# EvvGC_v1_1.net
KiCad netlist of a schematic drawn in Altium Designer
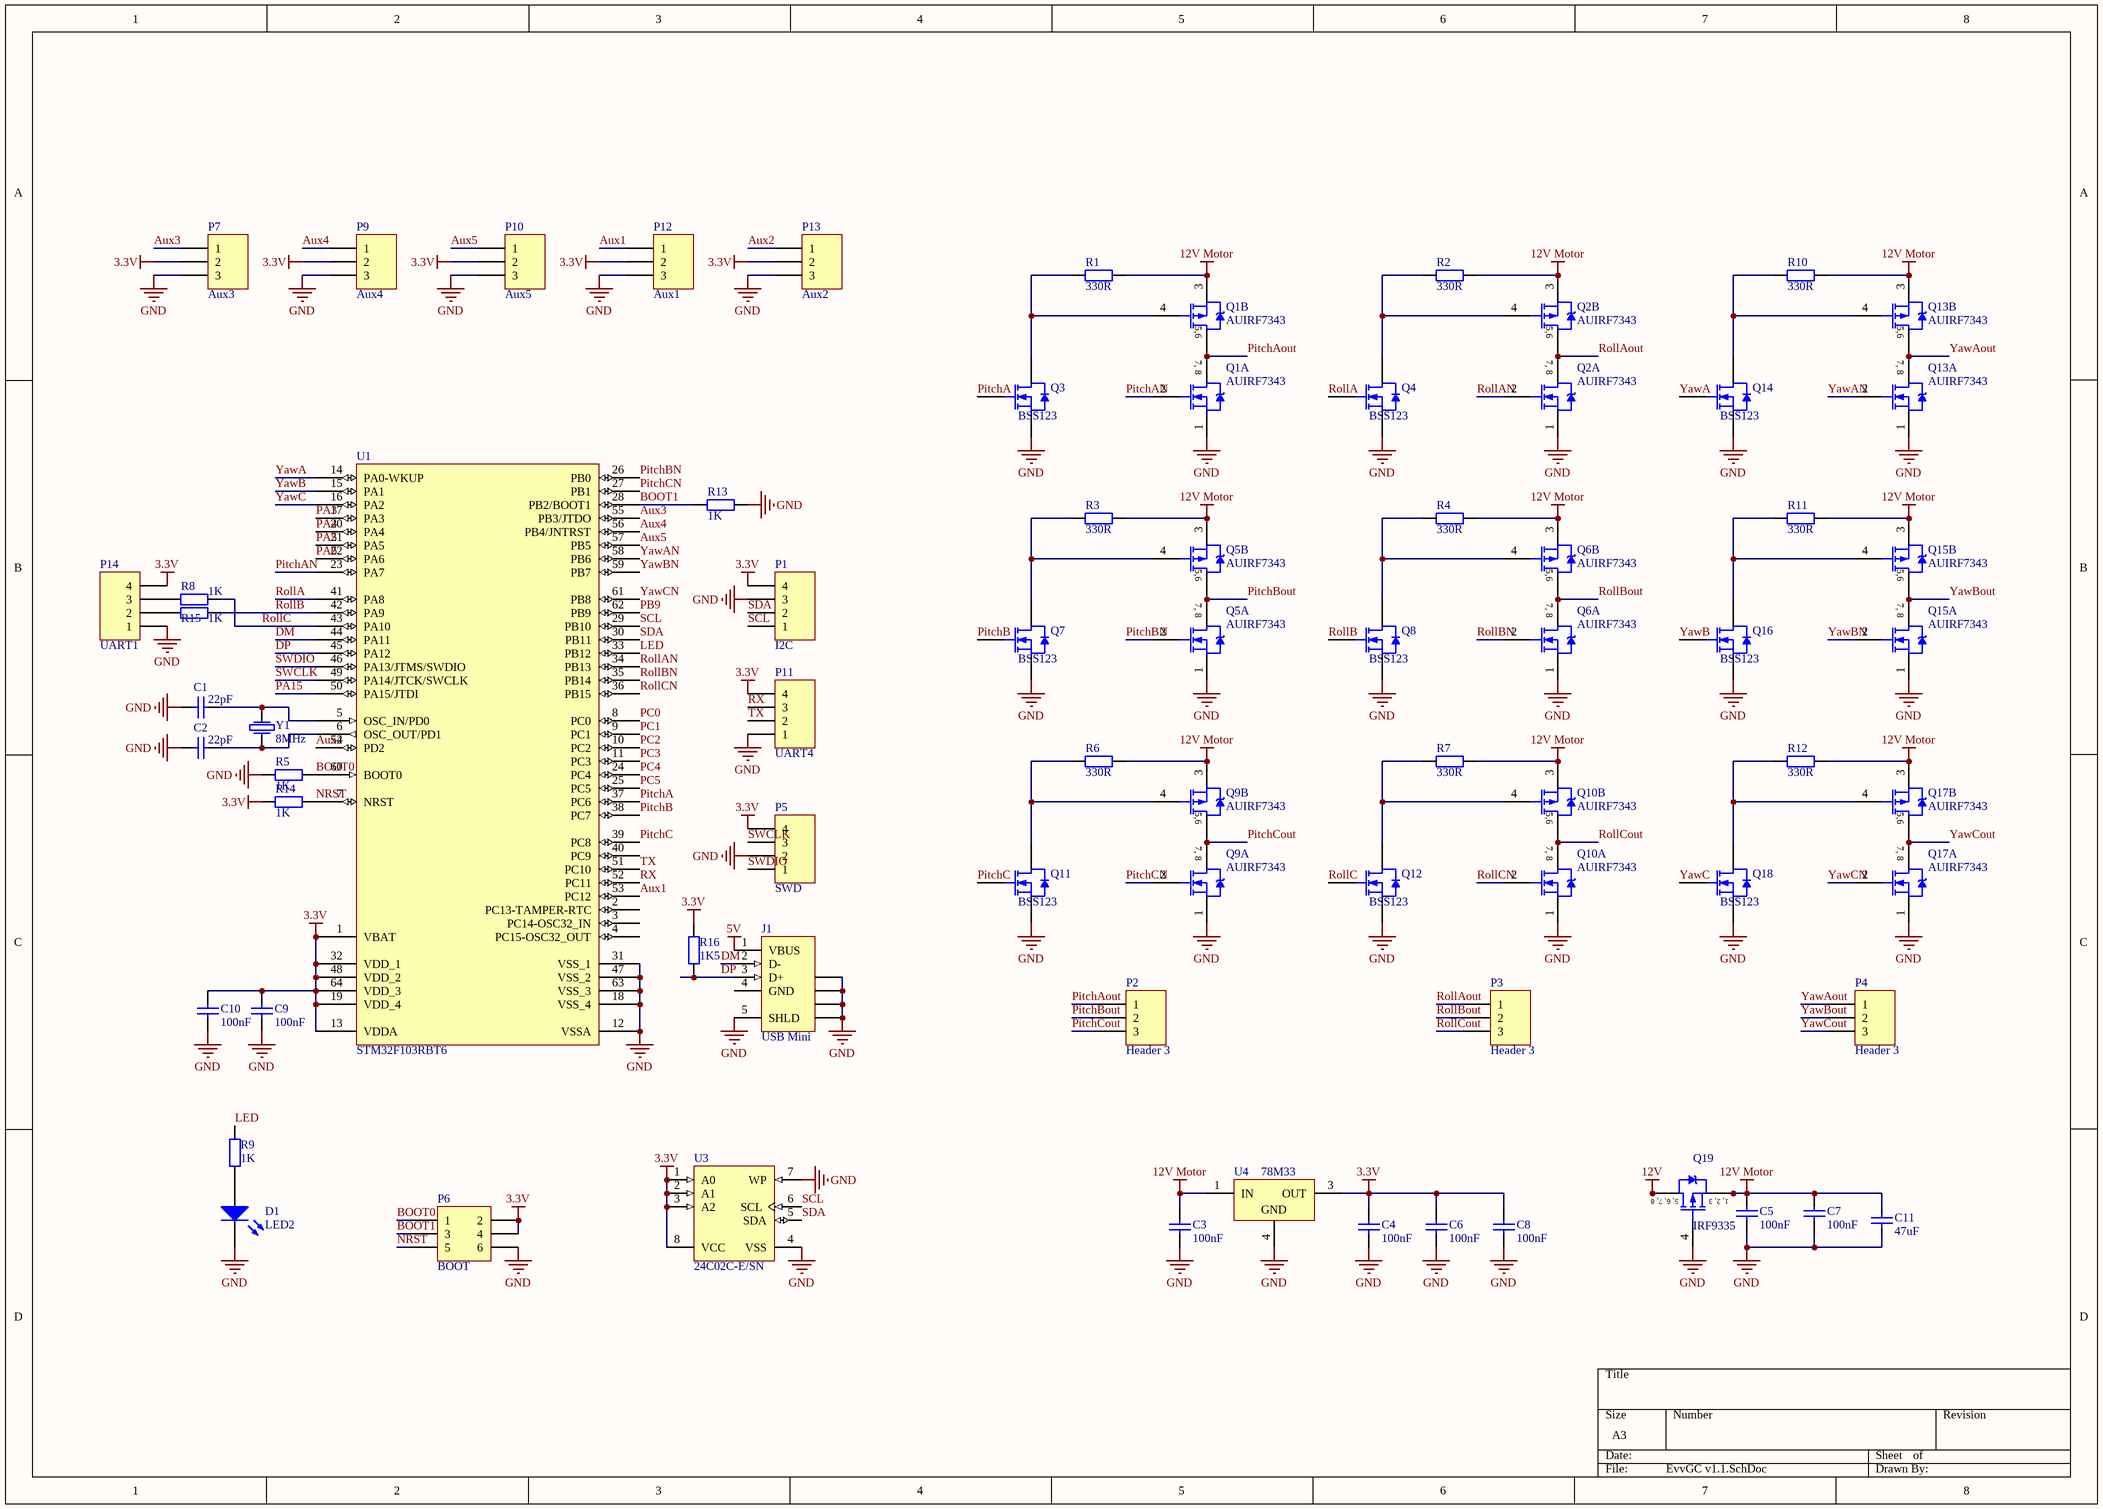
[diagram p0: EvvGC v1.1.SchDoc]

(export (version "E")
  (design (tool "Eeschema 10.0.6"))
  (components
    (comp (ref "C1")
      (value "22pF")
      (footprint "CAPC2012L")
      (description "Capacitor")
      (fields (field (name "Comment") "CAP0805") (field (name "PUBLISHER") "Altium Limited"))
      (libsource (lib "EMotus Components") (part "CAP0805"))
    )
    (comp (ref "C2")
      (value "22pF")
      (footprint "CAPC2012L")
      (description "Capacitor")
      (fields (field (name "Comment") "CAP0805") (field (name "PUBLISHER") "Altium Limited"))
      (libsource (lib "EMotus Components") (part "CAP0805"))
    )
    (comp (ref "C3")
      (value "100nF")
      (footprint "CAPC2012L")
      (description "Capacitor")
      (fields (field (name "Comment") "CAP0805") (field (name "PUBLISHER") "Altium Limited"))
      (libsource (lib "EMotus Components") (part "CAP0805"))
    )
    (comp (ref "C4")
      (value "100nF")
      (footprint "CAPC2012L")
      (description "Capacitor")
      (fields (field (name "Comment") "CAP0805") (field (name "PUBLISHER") "Altium Limited"))
      (libsource (lib "EMotus Components") (part "CAP0805"))
    )
    (comp (ref "C5")
      (value "100nF")
      (footprint "CAPC2012L")
      (description "Capacitor")
      (fields (field (name "Comment") "CAP0805") (field (name "PUBLISHER") "Altium Limited"))
      (libsource (lib "EMotus Components") (part "CAP0805"))
    )
    (comp (ref "C6")
      (value "100nF")
      (footprint "CAPC2012L")
      (description "Capacitor")
      (fields (field (name "Comment") "CAP0805") (field (name "PUBLISHER") "Altium Limited"))
      (libsource (lib "EMotus Components") (part "CAP0805"))
    )
    (comp (ref "C7")
      (value "100nF")
      (footprint "CAPC2012L")
      (description "Capacitor")
      (fields (field (name "Comment") "CAP0805") (field (name "PUBLISHER") "Altium Limited"))
      (libsource (lib "EMotus Components") (part "CAP0805"))
    )
    (comp (ref "C8")
      (value "100nF")
      (footprint "CAPC2012L")
      (description "Capacitor")
      (fields (field (name "Comment") "CAP0805") (field (name "PUBLISHER") "Altium Limited"))
      (libsource (lib "EMotus Components") (part "CAP0805"))
    )
    (comp (ref "C9")
      (value "100nF")
      (footprint "CAPC2012L")
      (description "Capacitor")
      (fields (field (name "Comment") "CAP0805") (field (name "PUBLISHER") "Altium Limited"))
      (libsource (lib "EMotus Components") (part "CAP0805"))
    )
    (comp (ref "C10")
      (value "100nF")
      (footprint "CAPC2012L")
      (description "Capacitor")
      (fields (field (name "Comment") "CAP0805") (field (name "PUBLISHER") "Altium Limited"))
      (libsource (lib "EMotus Components") (part "CAP0805"))
    )
    (comp (ref "C11")
      (value "47uF")
      (footprint "TC6032-2412")
      (description "Capacitor")
      (fields (field (name "PUBLISHER") "Altium Limited"))
      (libsource (lib "EMotus Components") (part "Cap"))
    )
    (comp (ref "D1")
      (value "LED2")
      (footprint "CAPC2012L")
      (description "Typical RED, GREEN, YELLOW, AMBER GaAs LED")
      (fields (field (name "PUBLISHER") "Altium Limited"))
      (libsource (lib "Miscellaneous Devices") (part "LED2"))
    )
    (comp (ref "J1")
      (value "USB Mini")
      (footprint "440247")
      (description "USB 2.0, Right Angle, SMT, B Type, Receptacle, 5 Position, Black")
      (fields (field (name "PUBLISHER") "Altium Limited"))
      (libsource (lib "AMP Serial Bus USB") (part "440247-2"))
    )
    (comp (ref "P1")
      (value "I2C")
      (footprint "HDR1X4")
      (description "Header, 4-Pin")
      (fields (field (name "PUBLISHER") "Altium Limited"))
      (libsource (lib "Miscellaneous Connectors") (part "Header 4"))
    )
    (comp (ref "P2")
      (value "Header 3")
      (footprint "HDR1X3")
      (description "Header, 3-Pin")
      (fields (field (name "PUBLISHER") "Altium Limited"))
      (libsource (lib "Miscellaneous Connectors") (part "Header 3"))
    )
    (comp (ref "P3")
      (value "Header 3")
      (footprint "HDR1X3")
      (description "Header, 3-Pin")
      (fields (field (name "PUBLISHER") "Altium Limited"))
      (libsource (lib "Miscellaneous Connectors") (part "Header 3"))
    )
    (comp (ref "P4")
      (value "Header 3")
      (footprint "HDR1X3")
      (description "Header, 3-Pin")
      (fields (field (name "PUBLISHER") "Altium Limited"))
      (libsource (lib "Miscellaneous Connectors") (part "Header 3"))
    )
    (comp (ref "P5")
      (value "SWD")
      (footprint "HDR1X4")
      (description "Header, 4-Pin")
      (fields (field (name "PUBLISHER") "Altium Limited"))
      (libsource (lib "Miscellaneous Connectors") (part "Header 4"))
    )
    (comp (ref "P6")
      (value "BOOT")
      (footprint "HDR2X3")
      (description "Header, 3-Pin, Dual row")
      (fields (field (name "PUBLISHER") "Altium Limited"))
      (libsource (lib "Miscellaneous Connectors") (part "Header 3X2"))
    )
    (comp (ref "P7")
      (value "Aux3")
      (footprint "HDR1X3")
      (description "Header, 3-Pin")
      (fields (field (name "PUBLISHER") "Altium Limited"))
      (libsource (lib "Miscellaneous Connectors") (part "Header 3"))
    )
    (comp (ref "P9")
      (value "Aux4")
      (footprint "HDR1X3")
      (description "Header, 3-Pin")
      (fields (field (name "PUBLISHER") "Altium Limited"))
      (libsource (lib "Miscellaneous Connectors") (part "Header 3"))
    )
    (comp (ref "P10")
      (value "Aux5")
      (footprint "HDR1X3")
      (description "Header, 3-Pin")
      (fields (field (name "PUBLISHER") "Altium Limited"))
      (libsource (lib "Miscellaneous Connectors") (part "Header 3"))
    )
    (comp (ref "P11")
      (value "UART4")
      (footprint "HDR1X4")
      (description "Header, 4-Pin")
      (fields (field (name "PUBLISHER") "Altium Limited"))
      (libsource (lib "Miscellaneous Connectors") (part "Header 4"))
    )
    (comp (ref "P12")
      (value "Aux1")
      (footprint "HDR1X3")
      (description "Header, 3-Pin")
      (fields (field (name "PUBLISHER") "Altium Limited"))
      (libsource (lib "Miscellaneous Connectors") (part "Header 3"))
    )
    (comp (ref "P13")
      (value "Aux2")
      (footprint "HDR1X3")
      (description "Header, 3-Pin")
      (fields (field (name "PUBLISHER") "Altium Limited"))
      (libsource (lib "Miscellaneous Connectors") (part "Header 3"))
    )
    (comp (ref "P14")
      (value "UART1")
      (footprint "HDR1X4")
      (description "Header, 4-Pin")
      (fields (field (name "PUBLISHER") "Altium Limited"))
      (libsource (lib "") (part "Header 4_1"))
    )
    (comp (ref "Q1")
      (value "AUIRF7343")
      (footprint "SO-8_N")
      (description "HEXFET Power MOSFET")
      (fields (field (name "PUBLISHER") "Altium Limited"))
      (libsource (lib "VMU") (part "AUIRF7343"))
    )
    (comp (ref "Q2")
      (value "AUIRF7343")
      (footprint "SO-8_N")
      (description "HEXFET Power MOSFET")
      (fields (field (name "PUBLISHER") "Altium Limited"))
      (libsource (lib "VMU") (part "AUIRF7343"))
    )
    (comp (ref "Q3")
      (value "BSS123")
      (footprint "SOT23_N_EM")
      (description "N-channel Enhancement Mode Field-effect Transistor")
      (fields (field (name "PUBLISHER") "Altium Limited"))
      (libsource (lib "EMotus Components") (part "2N7002"))
    )
    (comp (ref "Q4")
      (value "BSS123")
      (footprint "SOT23_N_EM")
      (description "N-channel Enhancement Mode Field-effect Transistor")
      (fields (field (name "PUBLISHER") "Altium Limited"))
      (libsource (lib "EMotus Components") (part "2N7002"))
    )
    (comp (ref "Q5")
      (value "AUIRF7343")
      (footprint "SO-8_N")
      (description "HEXFET Power MOSFET")
      (fields (field (name "PUBLISHER") "Altium Limited"))
      (libsource (lib "VMU") (part "AUIRF7343"))
    )
    (comp (ref "Q6")
      (value "AUIRF7343")
      (footprint "SO-8_N")
      (description "HEXFET Power MOSFET")
      (fields (field (name "PUBLISHER") "Altium Limited"))
      (libsource (lib "VMU") (part "AUIRF7343"))
    )
    (comp (ref "Q7")
      (value "BSS123")
      (footprint "SOT23_N_EM")
      (description "N-channel Enhancement Mode Field-effect Transistor")
      (fields (field (name "PUBLISHER") "Altium Limited"))
      (libsource (lib "EMotus Components") (part "2N7002"))
    )
    (comp (ref "Q8")
      (value "BSS123")
      (footprint "SOT23_N_EM")
      (description "N-channel Enhancement Mode Field-effect Transistor")
      (fields (field (name "PUBLISHER") "Altium Limited"))
      (libsource (lib "EMotus Components") (part "2N7002"))
    )
    (comp (ref "Q9")
      (value "AUIRF7343")
      (footprint "SO-8_N")
      (description "HEXFET Power MOSFET")
      (fields (field (name "PUBLISHER") "Altium Limited"))
      (libsource (lib "VMU") (part "AUIRF7343"))
    )
    (comp (ref "Q10")
      (value "AUIRF7343")
      (footprint "SO-8_N")
      (description "HEXFET Power MOSFET")
      (fields (field (name "PUBLISHER") "Altium Limited"))
      (libsource (lib "VMU") (part "AUIRF7343"))
    )
    (comp (ref "Q11")
      (value "BSS123")
      (footprint "SOT23_N_EM")
      (description "N-channel Enhancement Mode Field-effect Transistor")
      (fields (field (name "PUBLISHER") "Altium Limited"))
      (libsource (lib "EMotus Components") (part "2N7002"))
    )
    (comp (ref "Q12")
      (value "BSS123")
      (footprint "SOT23_N_EM")
      (description "N-channel Enhancement Mode Field-effect Transistor")
      (fields (field (name "PUBLISHER") "Altium Limited"))
      (libsource (lib "EMotus Components") (part "2N7002"))
    )
    (comp (ref "Q13")
      (value "AUIRF7343")
      (footprint "SO-8_N")
      (description "HEXFET Power MOSFET")
      (fields (field (name "PUBLISHER") "Altium Limited"))
      (libsource (lib "VMU") (part "AUIRF7343"))
    )
    (comp (ref "Q14")
      (value "BSS123")
      (footprint "SOT23_N_EM")
      (description "N-channel Enhancement Mode Field-effect Transistor")
      (fields (field (name "PUBLISHER") "Altium Limited"))
      (libsource (lib "EMotus Components") (part "2N7002"))
    )
    (comp (ref "Q15")
      (value "AUIRF7343")
      (footprint "SO-8_N")
      (description "HEXFET Power MOSFET")
      (fields (field (name "PUBLISHER") "Altium Limited"))
      (libsource (lib "VMU") (part "AUIRF7343"))
    )
    (comp (ref "Q16")
      (value "BSS123")
      (footprint "SOT23_N_EM")
      (description "N-channel Enhancement Mode Field-effect Transistor")
      (fields (field (name "PUBLISHER") "Altium Limited"))
      (libsource (lib "EMotus Components") (part "2N7002"))
    )
    (comp (ref "Q17")
      (value "AUIRF7343")
      (footprint "SO-8_N")
      (description "HEXFET Power MOSFET")
      (fields (field (name "PUBLISHER") "Altium Limited"))
      (libsource (lib "VMU") (part "AUIRF7343"))
    )
    (comp (ref "Q18")
      (value "BSS123")
      (footprint "SOT23_N_EM")
      (description "N-channel Enhancement Mode Field-effect Transistor")
      (fields (field (name "PUBLISHER") "Altium Limited"))
      (libsource (lib "EMotus Components") (part "2N7002"))
    )
    (comp (ref "Q19")
      (value "IRF9335")
      (footprint "SO-8_N")
      (description "HEXFET Power MOSFET")
      (fields
        (field (name "MANUFACTURER") "International Rectifier")
        (field (name "PART NUMBER") "IRF9335PBF")
        (field (name "PUBLISHER") "Altium Limited")
      )
      (libsource (lib "IR Discrete MOSFET - Power") (part "IRF7404"))
    )
    (comp (ref "R1")
      (value "330R")
      (footprint "C0805")
      (description "Resistor")
      (fields (field (name "PUBLISHER") "Altium Limited"))
      (libsource (lib "My Altium Lib") (part "Res"))
    )
    (comp (ref "R2")
      (value "330R")
      (footprint "C0805")
      (description "Resistor")
      (fields (field (name "PUBLISHER") "Altium Limited"))
      (libsource (lib "My Altium Lib") (part "Res"))
    )
    (comp (ref "R3")
      (value "330R")
      (footprint "C0805")
      (description "Resistor")
      (fields (field (name "PUBLISHER") "Altium Limited"))
      (libsource (lib "My Altium Lib") (part "Res"))
    )
    (comp (ref "R4")
      (value "330R")
      (footprint "C0805")
      (description "Resistor")
      (fields (field (name "PUBLISHER") "Altium Limited"))
      (libsource (lib "My Altium Lib") (part "Res"))
    )
    (comp (ref "R5")
      (value "1K")
      (footprint "RESC1608N")
      (description "RES 0603 1K")
      (fields (field (name "TOLERANCE") "±5%"))
      (libsource (lib "") (part "RES 0603 330R_1"))
    )
    (comp (ref "R6")
      (value "330R")
      (footprint "C0805")
      (description "Resistor")
      (fields (field (name "PUBLISHER") "Altium Limited"))
      (libsource (lib "My Altium Lib") (part "Res"))
    )
    (comp (ref "R7")
      (value "330R")
      (footprint "C0805")
      (description "Resistor")
      (fields (field (name "PUBLISHER") "Altium Limited"))
      (libsource (lib "My Altium Lib") (part "Res"))
    )
    (comp (ref "R8")
      (value "1K")
      (footprint "RESC1608N")
      (description "RES 0603 1K")
      (fields (field (name "TOLERANCE") "±5%"))
      (libsource (lib "") (part "RES 0603 330R_1"))
    )
    (comp (ref "R9")
      (value "1K")
      (footprint "RESC1608N")
      (description "RES 0603 1K")
      (fields (field (name "TOLERANCE") "±5%"))
      (libsource (lib "Resistors") (part "RES 0603 330R"))
    )
    (comp (ref "R10")
      (value "330R")
      (footprint "C0805")
      (description "Resistor")
      (fields (field (name "PUBLISHER") "Altium Limited"))
      (libsource (lib "My Altium Lib") (part "Res"))
    )
    (comp (ref "R11")
      (value "330R")
      (footprint "C0805")
      (description "Resistor")
      (fields (field (name "PUBLISHER") "Altium Limited"))
      (libsource (lib "My Altium Lib") (part "Res"))
    )
    (comp (ref "R12")
      (value "330R")
      (footprint "C0805")
      (description "Resistor")
      (fields (field (name "PUBLISHER") "Altium Limited"))
      (libsource (lib "My Altium Lib") (part "Res"))
    )
    (comp (ref "R13")
      (value "1K")
      (footprint "RESC1608N")
      (description "RES 0603 1K")
      (fields (field (name "TOLERANCE") "±5%"))
      (libsource (lib "") (part "RES 0603 330R_1"))
    )
    (comp (ref "R14")
      (value "1K")
      (footprint "RESC1608N")
      (description "RES 0603 1K")
      (fields (field (name "TOLERANCE") "±5%"))
      (libsource (lib "") (part "RES 0603 330R_1"))
    )
    (comp (ref "R15")
      (value "1K")
      (footprint "RESC1608N")
      (description "RES 0603 1K")
      (fields (field (name "TOLERANCE") "±5%"))
      (libsource (lib "") (part "RES 0603 330R_1"))
    )
    (comp (ref "R16")
      (value "1K5")
      (footprint "RESC1608N")
      (description "RES 0603 1K")
      (fields (field (name "TOLERANCE") "±5%"))
      (libsource (lib "Resistors") (part "RES 0603 330R"))
    )
    (comp (ref "U1")
      (value "STM32F103RBT6")
      (footprint "LQFP64_N")
      (description "STM32 ARM-based 32-bit MCU with 128 Kbytes Flash, 64-pin LQFP, Industrial Temperature")
      (fields (field (name "PUBLISHER") "Altium Limited"))
      (libsource (lib "ST Microcontroller 32-Bit STM32") (part "STM32F103RBT6"))
    )
    (comp (ref "U3")
      (value "24C02C-E/SN")
      (footprint "SOIC-SN8_N")
      (description "2Kbit, 400kHz, 5V, I2C Serial EEPROM, 8-Pin SOIC 150mil, Extended Temperature")
      (fields (field (name "PUBLISHER") "Altium Limited"))
      (libsource (lib "Microchip EEPROM I2C Serial") (part "24C02C-E/SN"))
    )
    (comp (ref "U4")
      (value "78M33")
      (footprint "TO-252")
      (description "Positive Voltage Regulator")
      (fields (field (name "PUBLISHER") "Altium Limited"))
      (libsource (lib "SMART LIB") (part "L78M05CDT"))
    )
    (comp (ref "Y1")
      (value "8MHz")
      (footprint "ABM3")
      (description "CRYSTAL 16M SMD5x3.2mm")
      (fields (field (name "MANUFACTURER") "ABRACON") (field (name "FARNELL PART NUMBER") "1611806"))
      (libsource (lib "elektromotus") (part "CRYSTAL 16M SMD5x3.2mm"))
    )
  )
  (nets
    (net (code "1") (name "/Aux1") (class "Default")
      (node (ref "P12") (pin "1") (pinfunction "1_1") (pintype "passive"))
      (node (ref "U1") (pin "53") (pinfunction "PC12_53") (pintype "bidirectional"))
    )
    (net (code "2") (name "/Aux2") (class "Default")
      (node (ref "P13") (pin "1") (pinfunction "1_1") (pintype "passive"))
      (node (ref "U1") (pin "54") (pinfunction "PD2_54") (pintype "bidirectional"))
    )
    (net (code "3") (name "/Aux3") (class "Default")
      (node (ref "P7") (pin "1") (pinfunction "1_1") (pintype "passive"))
      (node (ref "U1") (pin "55") (pinfunction "PB3/JTDO_55") (pintype "bidirectional"))
    )
    (net (code "4") (name "/Aux4") (class "Default")
      (node (ref "P9") (pin "1") (pinfunction "1_1") (pintype "passive"))
      (node (ref "U1") (pin "56") (pinfunction "PB4/JNTRST_56") (pintype "bidirectional"))
    )
    (net (code "5") (name "/Aux5") (class "Default")
      (node (ref "P10") (pin "1") (pinfunction "1_1") (pintype "passive"))
      (node (ref "U1") (pin "57") (pinfunction "PB5_57") (pintype "bidirectional"))
    )
    (net (code "6") (name "/BOOT0") (class "Default")
      (node (ref "P6") (pin "1") (pinfunction "1_1") (pintype "passive"))
      (node (ref "R5") (pin "1") (pinfunction "1_1") (pintype "passive"))
      (node (ref "U1") (pin "60") (pinfunction "BOOT0_60") (pintype "input"))
    )
    (net (code "7") (name "/BOOT1") (class "Default")
      (node (ref "P6") (pin "3") (pinfunction "3_3") (pintype "passive"))
      (node (ref "R13") (pin "2") (pinfunction "2_2") (pintype "passive"))
      (node (ref "U1") (pin "28") (pinfunction "PB2/BOOT1_28") (pintype "bidirectional"))
    )
    (net (code "8") (name "/DM") (class "Default")
      (node (ref "J1") (pin "2") (pinfunction "D-_2") (pintype "input"))
      (node (ref "U1") (pin "44") (pinfunction "PA11_44") (pintype "bidirectional"))
    )
    (net (code "9") (name "/DP") (class "Default")
      (node (ref "J1") (pin "3") (pinfunction "D+_3") (pintype "input"))
      (node (ref "R16") (pin "2") (pinfunction "2_2") (pintype "passive"))
      (node (ref "U1") (pin "45") (pinfunction "PA12_45") (pintype "bidirectional"))
    )
    (net (code "10") (name "/LED") (class "Default")
      (node (ref "R9") (pin "1") (pinfunction "1_1") (pintype "passive"))
      (node (ref "U1") (pin "33") (pinfunction "PB12_33") (pintype "bidirectional"))
    )
    (net (code "11") (name "/NRST") (class "Default")
      (node (ref "P6") (pin "5") (pinfunction "5_5") (pintype "passive"))
      (node (ref "R14") (pin "1") (pinfunction "1_1") (pintype "passive"))
      (node (ref "U1") (pin "7") (pinfunction "NRST_7") (pintype "bidirectional"))
    )
    (net (code "12") (name "/PA3") (class "Default")
      (node (ref "U1") (pin "17") (pinfunction "PA3_17") (pintype "bidirectional"))
    )
    (net (code "13") (name "/PA4") (class "Default")
      (node (ref "U1") (pin "20") (pinfunction "PA4_20") (pintype "bidirectional"))
    )
    (net (code "14") (name "/PA5") (class "Default")
      (node (ref "U1") (pin "21") (pinfunction "PA5_21") (pintype "bidirectional"))
    )
    (net (code "15") (name "/PA6") (class "Default")
      (node (ref "U1") (pin "22") (pinfunction "PA6_22") (pintype "bidirectional"))
    )
    (net (code "16") (name "/PA15") (class "Default")
      (node (ref "U1") (pin "50") (pinfunction "PA15/JTDI_50") (pintype "bidirectional"))
    )
    (net (code "17") (name "/PB9") (class "Default")
      (node (ref "U1") (pin "62") (pinfunction "PB9_62") (pintype "bidirectional"))
    )
    (net (code "18") (name "/PC0") (class "Default")
      (node (ref "U1") (pin "8") (pinfunction "PC0_8") (pintype "bidirectional"))
    )
    (net (code "19") (name "/PC1") (class "Default")
      (node (ref "U1") (pin "9") (pinfunction "PC1_9") (pintype "bidirectional"))
    )
    (net (code "20") (name "/PC2") (class "Default")
      (node (ref "U1") (pin "10") (pinfunction "PC2_10") (pintype "bidirectional"))
    )
    (net (code "21") (name "/PC3") (class "Default")
      (node (ref "U1") (pin "11") (pinfunction "PC3_11") (pintype "bidirectional"))
    )
    (net (code "22") (name "/PC4") (class "Default")
      (node (ref "U1") (pin "24") (pinfunction "PC4_24") (pintype "bidirectional"))
    )
    (net (code "23") (name "/PC5") (class "Default")
      (node (ref "U1") (pin "25") (pinfunction "PC5_25") (pintype "bidirectional"))
    )
    (net (code "24") (name "/PitchA") (class "Default")
      (node (ref "Q3") (pin "1") (pinfunction "G_1") (pintype "passive"))
      (node (ref "U1") (pin "37") (pinfunction "PC6_37") (pintype "bidirectional"))
    )
    (net (code "25") (name "/PitchAN") (class "Default")
      (node (ref "Q1") (pin "2") (pinfunction "G1_2") (pintype "passive"))
      (node (ref "U1") (pin "23") (pinfunction "PA7_23") (pintype "bidirectional"))
    )
    (net (code "26") (name "/PitchAout") (class "Default")
      (node (ref "P2") (pin "1") (pinfunction "1_1") (pintype "passive"))
      (node (ref "Q1") (pin "5") (pinfunction "D2_5") (pintype "passive"))
      (node (ref "Q1") (pin "6") (pinfunction "D2_6") (pintype "passive"))
      (node (ref "Q1") (pin "7") (pinfunction "D1_7") (pintype "passive"))
      (node (ref "Q1") (pin "8") (pinfunction "D1_8") (pintype "passive"))
    )
    (net (code "27") (name "/PitchB") (class "Default")
      (node (ref "Q7") (pin "1") (pinfunction "G_1") (pintype "passive"))
      (node (ref "U1") (pin "38") (pinfunction "PC7_38") (pintype "bidirectional"))
    )
    (net (code "28") (name "/PitchBN") (class "Default")
      (node (ref "Q5") (pin "2") (pinfunction "G1_2") (pintype "passive"))
      (node (ref "U1") (pin "26") (pinfunction "PB0_26") (pintype "bidirectional"))
    )
    (net (code "29") (name "/PitchBout") (class "Default")
      (node (ref "P2") (pin "2") (pinfunction "2_2") (pintype "passive"))
      (node (ref "Q5") (pin "5") (pinfunction "D2_5") (pintype "passive"))
      (node (ref "Q5") (pin "6") (pinfunction "D2_6") (pintype "passive"))
      (node (ref "Q5") (pin "7") (pinfunction "D1_7") (pintype "passive"))
      (node (ref "Q5") (pin "8") (pinfunction "D1_8") (pintype "passive"))
    )
    (net (code "30") (name "/PitchC") (class "Default")
      (node (ref "Q11") (pin "1") (pinfunction "G_1") (pintype "passive"))
      (node (ref "U1") (pin "39") (pinfunction "PC8_39") (pintype "bidirectional"))
    )
    (net (code "31") (name "/PitchCN") (class "Default")
      (node (ref "Q9") (pin "2") (pinfunction "G1_2") (pintype "passive"))
      (node (ref "U1") (pin "27") (pinfunction "PB1_27") (pintype "bidirectional"))
    )
    (net (code "32") (name "/PitchCout") (class "Default")
      (node (ref "P2") (pin "3") (pinfunction "3_3") (pintype "passive"))
      (node (ref "Q9") (pin "5") (pinfunction "D2_5") (pintype "passive"))
      (node (ref "Q9") (pin "6") (pinfunction "D2_6") (pintype "passive"))
      (node (ref "Q9") (pin "7") (pinfunction "D1_7") (pintype "passive"))
      (node (ref "Q9") (pin "8") (pinfunction "D1_8") (pintype "passive"))
    )
    (net (code "33") (name "/RX") (class "Default")
      (node (ref "P11") (pin "3") (pinfunction "3_3") (pintype "passive"))
      (node (ref "U1") (pin "52") (pinfunction "PC11_52") (pintype "bidirectional"))
    )
    (net (code "34") (name "/RollA") (class "Default")
      (node (ref "Q4") (pin "1") (pinfunction "G_1") (pintype "passive"))
      (node (ref "U1") (pin "41") (pinfunction "PA8_41") (pintype "bidirectional"))
    )
    (net (code "35") (name "/RollAN") (class "Default")
      (node (ref "Q2") (pin "2") (pinfunction "G1_2") (pintype "passive"))
      (node (ref "U1") (pin "34") (pinfunction "PB13_34") (pintype "bidirectional"))
    )
    (net (code "36") (name "/RollAout") (class "Default")
      (node (ref "P3") (pin "1") (pinfunction "1_1") (pintype "passive"))
      (node (ref "Q2") (pin "5") (pinfunction "D2_5") (pintype "passive"))
      (node (ref "Q2") (pin "6") (pinfunction "D2_6") (pintype "passive"))
      (node (ref "Q2") (pin "7") (pinfunction "D1_7") (pintype "passive"))
      (node (ref "Q2") (pin "8") (pinfunction "D1_8") (pintype "passive"))
    )
    (net (code "37") (name "/RollB") (class "Default")
      (node (ref "Q8") (pin "1") (pinfunction "G_1") (pintype "passive"))
      (node (ref "R15") (pin "1") (pinfunction "1_1") (pintype "passive"))
      (node (ref "U1") (pin "42") (pinfunction "PA9_42") (pintype "bidirectional"))
    )
    (net (code "38") (name "/RollBN") (class "Default")
      (node (ref "Q6") (pin "2") (pinfunction "G1_2") (pintype "passive"))
      (node (ref "U1") (pin "35") (pinfunction "PB14_35") (pintype "bidirectional"))
    )
    (net (code "39") (name "/RollBout") (class "Default")
      (node (ref "P3") (pin "2") (pinfunction "2_2") (pintype "passive"))
      (node (ref "Q6") (pin "5") (pinfunction "D2_5") (pintype "passive"))
      (node (ref "Q6") (pin "6") (pinfunction "D2_6") (pintype "passive"))
      (node (ref "Q6") (pin "7") (pinfunction "D1_7") (pintype "passive"))
      (node (ref "Q6") (pin "8") (pinfunction "D1_8") (pintype "passive"))
    )
    (net (code "40") (name "/RollC") (class "Default")
      (node (ref "Q12") (pin "1") (pinfunction "G_1") (pintype "passive"))
      (node (ref "R8") (pin "1") (pinfunction "1_1") (pintype "passive"))
      (node (ref "U1") (pin "43") (pinfunction "PA10_43") (pintype "bidirectional"))
    )
    (net (code "41") (name "/RollCN") (class "Default")
      (node (ref "Q10") (pin "2") (pinfunction "G1_2") (pintype "passive"))
      (node (ref "U1") (pin "36") (pinfunction "PB15_36") (pintype "bidirectional"))
    )
    (net (code "42") (name "/RollCout") (class "Default")
      (node (ref "P3") (pin "3") (pinfunction "3_3") (pintype "passive"))
      (node (ref "Q10") (pin "5") (pinfunction "D2_5") (pintype "passive"))
      (node (ref "Q10") (pin "6") (pinfunction "D2_6") (pintype "passive"))
      (node (ref "Q10") (pin "7") (pinfunction "D1_7") (pintype "passive"))
      (node (ref "Q10") (pin "8") (pinfunction "D1_8") (pintype "passive"))
    )
    (net (code "43") (name "/SCL") (class "Default")
      (node (ref "P1") (pin "1") (pinfunction "1_1") (pintype "passive"))
      (node (ref "U1") (pin "29") (pinfunction "PB10_29") (pintype "bidirectional"))
      (node (ref "U3") (pin "6") (pinfunction "SCL_6") (pintype "input"))
    )
    (net (code "44") (name "/SDA") (class "Default")
      (node (ref "P1") (pin "2") (pinfunction "2_2") (pintype "passive"))
      (node (ref "U1") (pin "30") (pinfunction "PB11_30") (pintype "bidirectional"))
      (node (ref "U3") (pin "5") (pinfunction "SDA_5") (pintype "bidirectional"))
    )
    (net (code "45") (name "/SWCLK") (class "Default")
      (node (ref "P5") (pin "3") (pinfunction "3_3") (pintype "passive"))
      (node (ref "U1") (pin "49") (pinfunction "PA14/JTCK/SWCLK_49") (pintype "bidirectional"))
    )
    (net (code "46") (name "/SWDIO") (class "Default")
      (node (ref "P5") (pin "1") (pinfunction "1_1") (pintype "passive"))
      (node (ref "U1") (pin "46") (pinfunction "PA13/JTMS/SWDIO_46") (pintype "bidirectional"))
    )
    (net (code "47") (name "/TX") (class "Default")
      (node (ref "P11") (pin "2") (pinfunction "2_2") (pintype "passive"))
      (node (ref "U1") (pin "51") (pinfunction "PC10_51") (pintype "bidirectional"))
    )
    (net (code "48") (name "/YawA") (class "Default")
      (node (ref "Q14") (pin "1") (pinfunction "G_1") (pintype "passive"))
      (node (ref "U1") (pin "14") (pinfunction "PA0-WKUP_14") (pintype "bidirectional"))
    )
    (net (code "49") (name "/YawAN") (class "Default")
      (node (ref "Q13") (pin "2") (pinfunction "G1_2") (pintype "passive"))
      (node (ref "U1") (pin "58") (pinfunction "PB6_58") (pintype "bidirectional"))
    )
    (net (code "50") (name "/YawAout") (class "Default")
      (node (ref "P4") (pin "1") (pinfunction "1_1") (pintype "passive"))
      (node (ref "Q13") (pin "5") (pinfunction "D2_5") (pintype "passive"))
      (node (ref "Q13") (pin "6") (pinfunction "D2_6") (pintype "passive"))
      (node (ref "Q13") (pin "7") (pinfunction "D1_7") (pintype "passive"))
      (node (ref "Q13") (pin "8") (pinfunction "D1_8") (pintype "passive"))
    )
    (net (code "51") (name "/YawB") (class "Default")
      (node (ref "Q16") (pin "1") (pinfunction "G_1") (pintype "passive"))
      (node (ref "U1") (pin "15") (pinfunction "PA1_15") (pintype "bidirectional"))
    )
    (net (code "52") (name "/YawBN") (class "Default")
      (node (ref "Q15") (pin "2") (pinfunction "G1_2") (pintype "passive"))
      (node (ref "U1") (pin "59") (pinfunction "PB7_59") (pintype "bidirectional"))
    )
    (net (code "53") (name "/YawBout") (class "Default")
      (node (ref "P4") (pin "2") (pinfunction "2_2") (pintype "passive"))
      (node (ref "Q15") (pin "5") (pinfunction "D2_5") (pintype "passive"))
      (node (ref "Q15") (pin "6") (pinfunction "D2_6") (pintype "passive"))
      (node (ref "Q15") (pin "7") (pinfunction "D1_7") (pintype "passive"))
      (node (ref "Q15") (pin "8") (pinfunction "D1_8") (pintype "passive"))
    )
    (net (code "54") (name "/YawC") (class "Default")
      (node (ref "Q18") (pin "1") (pinfunction "G_1") (pintype "passive"))
      (node (ref "U1") (pin "16") (pinfunction "PA2_16") (pintype "bidirectional"))
    )
    (net (code "55") (name "/YawCN") (class "Default")
      (node (ref "Q17") (pin "2") (pinfunction "G1_2") (pintype "passive"))
      (node (ref "U1") (pin "61") (pinfunction "PB8_61") (pintype "bidirectional"))
    )
    (net (code "56") (name "/YawCout") (class "Default")
      (node (ref "P4") (pin "3") (pinfunction "3_3") (pintype "passive"))
      (node (ref "Q17") (pin "5") (pinfunction "D2_5") (pintype "passive"))
      (node (ref "Q17") (pin "6") (pinfunction "D2_6") (pintype "passive"))
      (node (ref "Q17") (pin "7") (pinfunction "D1_7") (pintype "passive"))
      (node (ref "Q17") (pin "8") (pinfunction "D1_8") (pintype "passive"))
    )
    (net (code "57") (name "3.3V") (class "Default")
      (node (ref "C10") (pin "1") (pinfunction "1_1") (pintype "passive"))
      (node (ref "C4") (pin "1") (pinfunction "1_1") (pintype "passive"))
      (node (ref "C6") (pin "1") (pinfunction "1_1") (pintype "passive"))
      (node (ref "C8") (pin "1") (pinfunction "1_1") (pintype "passive"))
      (node (ref "C9") (pin "1") (pinfunction "1_1") (pintype "passive"))
      (node (ref "P1") (pin "4") (pinfunction "4_4") (pintype "passive"))
      (node (ref "P10") (pin "2") (pinfunction "2_2") (pintype "passive"))
      (node (ref "P11") (pin "4") (pinfunction "4_4") (pintype "passive"))
      (node (ref "P12") (pin "2") (pinfunction "2_2") (pintype "passive"))
      (node (ref "P13") (pin "2") (pinfunction "2_2") (pintype "passive"))
      (node (ref "P14") (pin "4") (pinfunction "4_4") (pintype "passive"))
      (node (ref "P5") (pin "4") (pinfunction "4_4") (pintype "passive"))
      (node (ref "P6") (pin "2") (pinfunction "2_2") (pintype "passive"))
      (node (ref "P6") (pin "4") (pinfunction "4_4") (pintype "passive"))
      (node (ref "P7") (pin "2") (pinfunction "2_2") (pintype "passive"))
      (node (ref "P9") (pin "2") (pinfunction "2_2") (pintype "passive"))
      (node (ref "R14") (pin "2") (pinfunction "2_2") (pintype "passive"))
      (node (ref "R16") (pin "1") (pinfunction "1_1") (pintype "passive"))
      (node (ref "U1") (pin "1") (pinfunction "VBAT_1") (pintype "power_in"))
      (node (ref "U1") (pin "13") (pinfunction "VDDA_13") (pintype "power_in"))
      (node (ref "U1") (pin "19") (pinfunction "VDD_4_19") (pintype "power_in"))
      (node (ref "U1") (pin "32") (pinfunction "VDD_1_32") (pintype "power_in"))
      (node (ref "U1") (pin "48") (pinfunction "VDD_2_48") (pintype "power_in"))
      (node (ref "U1") (pin "64") (pinfunction "VDD_3_64") (pintype "power_in"))
      (node (ref "U3") (pin "1") (pinfunction "A0_1") (pintype "input"))
      (node (ref "U3") (pin "2") (pinfunction "A1_2") (pintype "input"))
      (node (ref "U3") (pin "3") (pinfunction "A2_3") (pintype "input"))
      (node (ref "U3") (pin "8") (pinfunction "VCC_8") (pintype "power_in"))
      (node (ref "U4") (pin "3") (pinfunction "OUT_3") (pintype "power_in"))
    )
    (net (code "58") (name "5V") (class "Default")
      (node (ref "J1") (pin "1") (pinfunction "VBUS_1") (pintype "power_in"))
    )
    (net (code "59") (name "12V") (class "Default")
      (node (ref "Q19") (pin "5") (pinfunction "D_5") (pintype "passive"))
      (node (ref "Q19") (pin "6") (pinfunction "D_6") (pintype "passive"))
      (node (ref "Q19") (pin "7") (pinfunction "D_7") (pintype "passive"))
      (node (ref "Q19") (pin "8") (pinfunction "D_8") (pintype "passive"))
    )
    (net (code "60") (name "12V Motor") (class "Default")
      (node (ref "C11") (pin "2") (pinfunction "2_2") (pintype "passive"))
      (node (ref "C3") (pin "1") (pinfunction "1_1") (pintype "passive"))
      (node (ref "C5") (pin "1") (pinfunction "1_1") (pintype "passive"))
      (node (ref "C7") (pin "1") (pinfunction "1_1") (pintype "passive"))
      (node (ref "Q1") (pin "3") (pinfunction "S2_3") (pintype "passive"))
      (node (ref "Q10") (pin "3") (pinfunction "S2_3") (pintype "passive"))
      (node (ref "Q13") (pin "3") (pinfunction "S2_3") (pintype "passive"))
      (node (ref "Q15") (pin "3") (pinfunction "S2_3") (pintype "passive"))
      (node (ref "Q17") (pin "3") (pinfunction "S2_3") (pintype "passive"))
      (node (ref "Q19") (pin "1") (pinfunction "S_1") (pintype "passive"))
      (node (ref "Q19") (pin "2") (pinfunction "S_2") (pintype "passive"))
      (node (ref "Q19") (pin "3") (pinfunction "S_3") (pintype "passive"))
      (node (ref "Q2") (pin "3") (pinfunction "S2_3") (pintype "passive"))
      (node (ref "Q5") (pin "3") (pinfunction "S2_3") (pintype "passive"))
      (node (ref "Q6") (pin "3") (pinfunction "S2_3") (pintype "passive"))
      (node (ref "Q9") (pin "3") (pinfunction "S2_3") (pintype "passive"))
      (node (ref "R1") (pin "2") (pinfunction "2_2") (pintype "passive"))
      (node (ref "R10") (pin "2") (pinfunction "2_2") (pintype "passive"))
      (node (ref "R11") (pin "2") (pinfunction "2_2") (pintype "passive"))
      (node (ref "R12") (pin "2") (pinfunction "2_2") (pintype "passive"))
      (node (ref "R2") (pin "2") (pinfunction "2_2") (pintype "passive"))
      (node (ref "R3") (pin "2") (pinfunction "2_2") (pintype "passive"))
      (node (ref "R4") (pin "2") (pinfunction "2_2") (pintype "passive"))
      (node (ref "R6") (pin "2") (pinfunction "2_2") (pintype "passive"))
      (node (ref "R7") (pin "2") (pinfunction "2_2") (pintype "passive"))
      (node (ref "U4") (pin "1") (pinfunction "IN_1") (pintype "power_in"))
    )
    (net (code "61") (name "GND") (class "Default")
      (node (ref "C1") (pin "2") (pinfunction "2_2") (pintype "passive"))
      (node (ref "C10") (pin "2") (pinfunction "2_2") (pintype "passive"))
      (node (ref "C11") (pin "1") (pinfunction "1_1") (pintype "passive"))
      (node (ref "C2") (pin "2") (pinfunction "2_2") (pintype "passive"))
      (node (ref "C3") (pin "2") (pinfunction "2_2") (pintype "passive"))
      (node (ref "C4") (pin "2") (pinfunction "2_2") (pintype "passive"))
      (node (ref "C5") (pin "2") (pinfunction "2_2") (pintype "passive"))
      (node (ref "C6") (pin "2") (pinfunction "2_2") (pintype "passive"))
      (node (ref "C7") (pin "2") (pinfunction "2_2") (pintype "passive"))
      (node (ref "C8") (pin "2") (pinfunction "2_2") (pintype "passive"))
      (node (ref "C9") (pin "2") (pinfunction "2_2") (pintype "passive"))
      (node (ref "D1") (pin "2") (pinfunction "K_2") (pintype "passive"))
      (node (ref "J1") (pin "5") (pinfunction "SHLD_5") (pintype "passive"))
      (node (ref "J1") (pin "6") (pinfunction "SHLD_6") (pintype "passive"))
      (node (ref "J1") (pin "7") (pinfunction "SHLD_7") (pintype "passive"))
      (node (ref "J1") (pin "8") (pinfunction "SHLD_8") (pintype "passive"))
      (node (ref "J1") (pin "9") (pinfunction "SHLD_9") (pintype "passive"))
      (node (ref "P1") (pin "3") (pinfunction "3_3") (pintype "passive"))
      (node (ref "P10") (pin "3") (pinfunction "3_3") (pintype "passive"))
      (node (ref "P11") (pin "1") (pinfunction "1_1") (pintype "passive"))
      (node (ref "P12") (pin "3") (pinfunction "3_3") (pintype "passive"))
      (node (ref "P13") (pin "3") (pinfunction "3_3") (pintype "passive"))
      (node (ref "P14") (pin "1") (pinfunction "1_1") (pintype "passive"))
      (node (ref "P5") (pin "2") (pinfunction "2_2") (pintype "passive"))
      (node (ref "P6") (pin "6") (pinfunction "6_6") (pintype "passive"))
      (node (ref "P7") (pin "3") (pinfunction "3_3") (pintype "passive"))
      (node (ref "P9") (pin "3") (pinfunction "3_3") (pintype "passive"))
      (node (ref "Q1") (pin "1") (pinfunction "S1_1") (pintype "passive"))
      (node (ref "Q10") (pin "1") (pinfunction "S1_1") (pintype "passive"))
      (node (ref "Q11") (pin "2") (pinfunction "S_2") (pintype "passive"))
      (node (ref "Q12") (pin "2") (pinfunction "S_2") (pintype "passive"))
      (node (ref "Q13") (pin "1") (pinfunction "S1_1") (pintype "passive"))
      (node (ref "Q14") (pin "2") (pinfunction "S_2") (pintype "passive"))
      (node (ref "Q15") (pin "1") (pinfunction "S1_1") (pintype "passive"))
      (node (ref "Q16") (pin "2") (pinfunction "S_2") (pintype "passive"))
      (node (ref "Q17") (pin "1") (pinfunction "S1_1") (pintype "passive"))
      (node (ref "Q18") (pin "2") (pinfunction "S_2") (pintype "passive"))
      (node (ref "Q19") (pin "4") (pinfunction "G_4") (pintype "passive"))
      (node (ref "Q2") (pin "1") (pinfunction "S1_1") (pintype "passive"))
      (node (ref "Q3") (pin "2") (pinfunction "S_2") (pintype "passive"))
      (node (ref "Q4") (pin "2") (pinfunction "S_2") (pintype "passive"))
      (node (ref "Q5") (pin "1") (pinfunction "S1_1") (pintype "passive"))
      (node (ref "Q6") (pin "1") (pinfunction "S1_1") (pintype "passive"))
      (node (ref "Q7") (pin "2") (pinfunction "S_2") (pintype "passive"))
      (node (ref "Q8") (pin "2") (pinfunction "S_2") (pintype "passive"))
      (node (ref "Q9") (pin "1") (pinfunction "S1_1") (pintype "passive"))
      (node (ref "R13") (pin "1") (pinfunction "1_1") (pintype "passive"))
      (node (ref "R5") (pin "2") (pinfunction "2_2") (pintype "passive"))
      (node (ref "U1") (pin "12") (pinfunction "VSSA_12") (pintype "power_in"))
      (node (ref "U1") (pin "18") (pinfunction "VSS_4_18") (pintype "power_in"))
      (node (ref "U1") (pin "31") (pinfunction "VSS_1_31") (pintype "power_in"))
      (node (ref "U1") (pin "47") (pinfunction "VSS_2_47") (pintype "power_in"))
      (node (ref "U1") (pin "63") (pinfunction "VSS_3_63") (pintype "power_in"))
      (node (ref "U3") (pin "4") (pinfunction "VSS_4") (pintype "power_in"))
      (node (ref "U3") (pin "7") (pinfunction "WP_7") (pintype "input"))
      (node (ref "U4") (pin "4") (pinfunction "GND_4") (pintype "power_in"))
    )
    (net (code "62") (name "Net-(D1-A)") (class "Default")
      (node (ref "D1") (pin "1") (pinfunction "A_1") (pintype "passive"))
      (node (ref "R9") (pin "2") (pinfunction "2_2") (pintype "passive"))
    )
    (net (code "63") (name "Net-(P14-Pad2)") (class "Default")
      (node (ref "P14") (pin "2") (pinfunction "2_2") (pintype "passive"))
      (node (ref "R15") (pin "2") (pinfunction "2_2") (pintype "passive"))
    )
    (net (code "64") (name "Net-(P14-Pad3)") (class "Default")
      (node (ref "P14") (pin "3") (pinfunction "3_3") (pintype "passive"))
      (node (ref "R8") (pin "2") (pinfunction "2_2") (pintype "passive"))
    )
    (net (code "65") (name "Net-(Q1B-G2)") (class "Default")
      (node (ref "Q1") (pin "4") (pinfunction "G2_4") (pintype "passive"))
      (node (ref "Q3") (pin "3") (pinfunction "20_3") (pintype "passive"))
      (node (ref "R1") (pin "1") (pinfunction "1_1") (pintype "passive"))
    )
    (net (code "66") (name "Net-(Q2B-G2)") (class "Default")
      (node (ref "Q2") (pin "4") (pinfunction "G2_4") (pintype "passive"))
      (node (ref "Q4") (pin "3") (pinfunction "20_3") (pintype "passive"))
      (node (ref "R2") (pin "1") (pinfunction "1_1") (pintype "passive"))
    )
    (net (code "67") (name "Net-(Q5B-G2)") (class "Default")
      (node (ref "Q5") (pin "4") (pinfunction "G2_4") (pintype "passive"))
      (node (ref "Q7") (pin "3") (pinfunction "20_3") (pintype "passive"))
      (node (ref "R3") (pin "1") (pinfunction "1_1") (pintype "passive"))
    )
    (net (code "68") (name "Net-(Q6B-G2)") (class "Default")
      (node (ref "Q6") (pin "4") (pinfunction "G2_4") (pintype "passive"))
      (node (ref "Q8") (pin "3") (pinfunction "20_3") (pintype "passive"))
      (node (ref "R4") (pin "1") (pinfunction "1_1") (pintype "passive"))
    )
    (net (code "69") (name "Net-(Q10B-G2)") (class "Default")
      (node (ref "Q10") (pin "4") (pinfunction "G2_4") (pintype "passive"))
      (node (ref "Q12") (pin "3") (pinfunction "20_3") (pintype "passive"))
      (node (ref "R7") (pin "1") (pinfunction "1_1") (pintype "passive"))
    )
    (net (code "70") (name "Net-(Q11-20)") (class "Default")
      (node (ref "Q11") (pin "3") (pinfunction "20_3") (pintype "passive"))
      (node (ref "Q9") (pin "4") (pinfunction "G2_4") (pintype "passive"))
      (node (ref "R6") (pin "1") (pinfunction "1_1") (pintype "passive"))
    )
    (net (code "71") (name "Net-(Q13B-G2)") (class "Default")
      (node (ref "Q13") (pin "4") (pinfunction "G2_4") (pintype "passive"))
      (node (ref "Q14") (pin "3") (pinfunction "20_3") (pintype "passive"))
      (node (ref "R10") (pin "1") (pinfunction "1_1") (pintype "passive"))
    )
    (net (code "72") (name "Net-(Q15B-G2)") (class "Default")
      (node (ref "Q15") (pin "4") (pinfunction "G2_4") (pintype "passive"))
      (node (ref "Q16") (pin "3") (pinfunction "20_3") (pintype "passive"))
      (node (ref "R11") (pin "1") (pinfunction "1_1") (pintype "passive"))
    )
    (net (code "73") (name "Net-(Q17B-G2)") (class "Default")
      (node (ref "Q17") (pin "4") (pinfunction "G2_4") (pintype "passive"))
      (node (ref "Q18") (pin "3") (pinfunction "20_3") (pintype "passive"))
      (node (ref "R12") (pin "1") (pinfunction "1_1") (pintype "passive"))
    )
    (net (code "74") (name "Net-(U1-OSC_IN{slash}PD0)") (class "Default")
      (node (ref "C1") (pin "1") (pinfunction "1_1") (pintype "passive"))
      (node (ref "U1") (pin "5") (pinfunction "OSC_IN/PD0_5") (pintype "input"))
      (node (ref "Y1") (pin "1") (pinfunction "1_1") (pintype "passive"))
    )
    (net (code "75") (name "Net-(U1-OSC_OUT{slash}PD1)") (class "Default")
      (node (ref "C2") (pin "1") (pinfunction "1_1") (pintype "passive"))
      (node (ref "U1") (pin "6") (pinfunction "OSC_OUT/PD1_6") (pintype "output"))
      (node (ref "Y1") (pin "2") (pinfunction "2_2") (pintype "passive"))
    )
    (net (code "76") (name "unconnected-(J1-GND-Pad4)") (class "Default")
      (node (ref "J1") (pin "4") (pinfunction "GND_4") (pintype "power_in"))
    )
    (net (code "77") (name "unconnected-(U1-PC9-Pad40)") (class "Default")
      (node (ref "U1") (pin "40") (pinfunction "PC9_40") (pintype "bidirectional"))
    )
    (net (code "78") (name "unconnected-(U1-PC13-TAMPER-RTC-Pad2)") (class "Default")
      (node (ref "U1") (pin "2") (pinfunction "PC13-TAMPER-RTC_2") (pintype "bidirectional"))
    )
    (net (code "79") (name "unconnected-(U1-PC14-OSC32_IN-Pad3)") (class "Default")
      (node (ref "U1") (pin "3") (pinfunction "PC14-OSC32_IN_3") (pintype "bidirectional"))
    )
    (net (code "80") (name "unconnected-(U1-PC15-OSC32_OUT-Pad4)") (class "Default")
      (node (ref "U1") (pin "4") (pinfunction "PC15-OSC32_OUT_4") (pintype "bidirectional"))
    )
  )
)
